# Adafruit_NeoPixel_Ring_16_rev_C.net
KiCad netlist of a schematic drawn in EAGLE
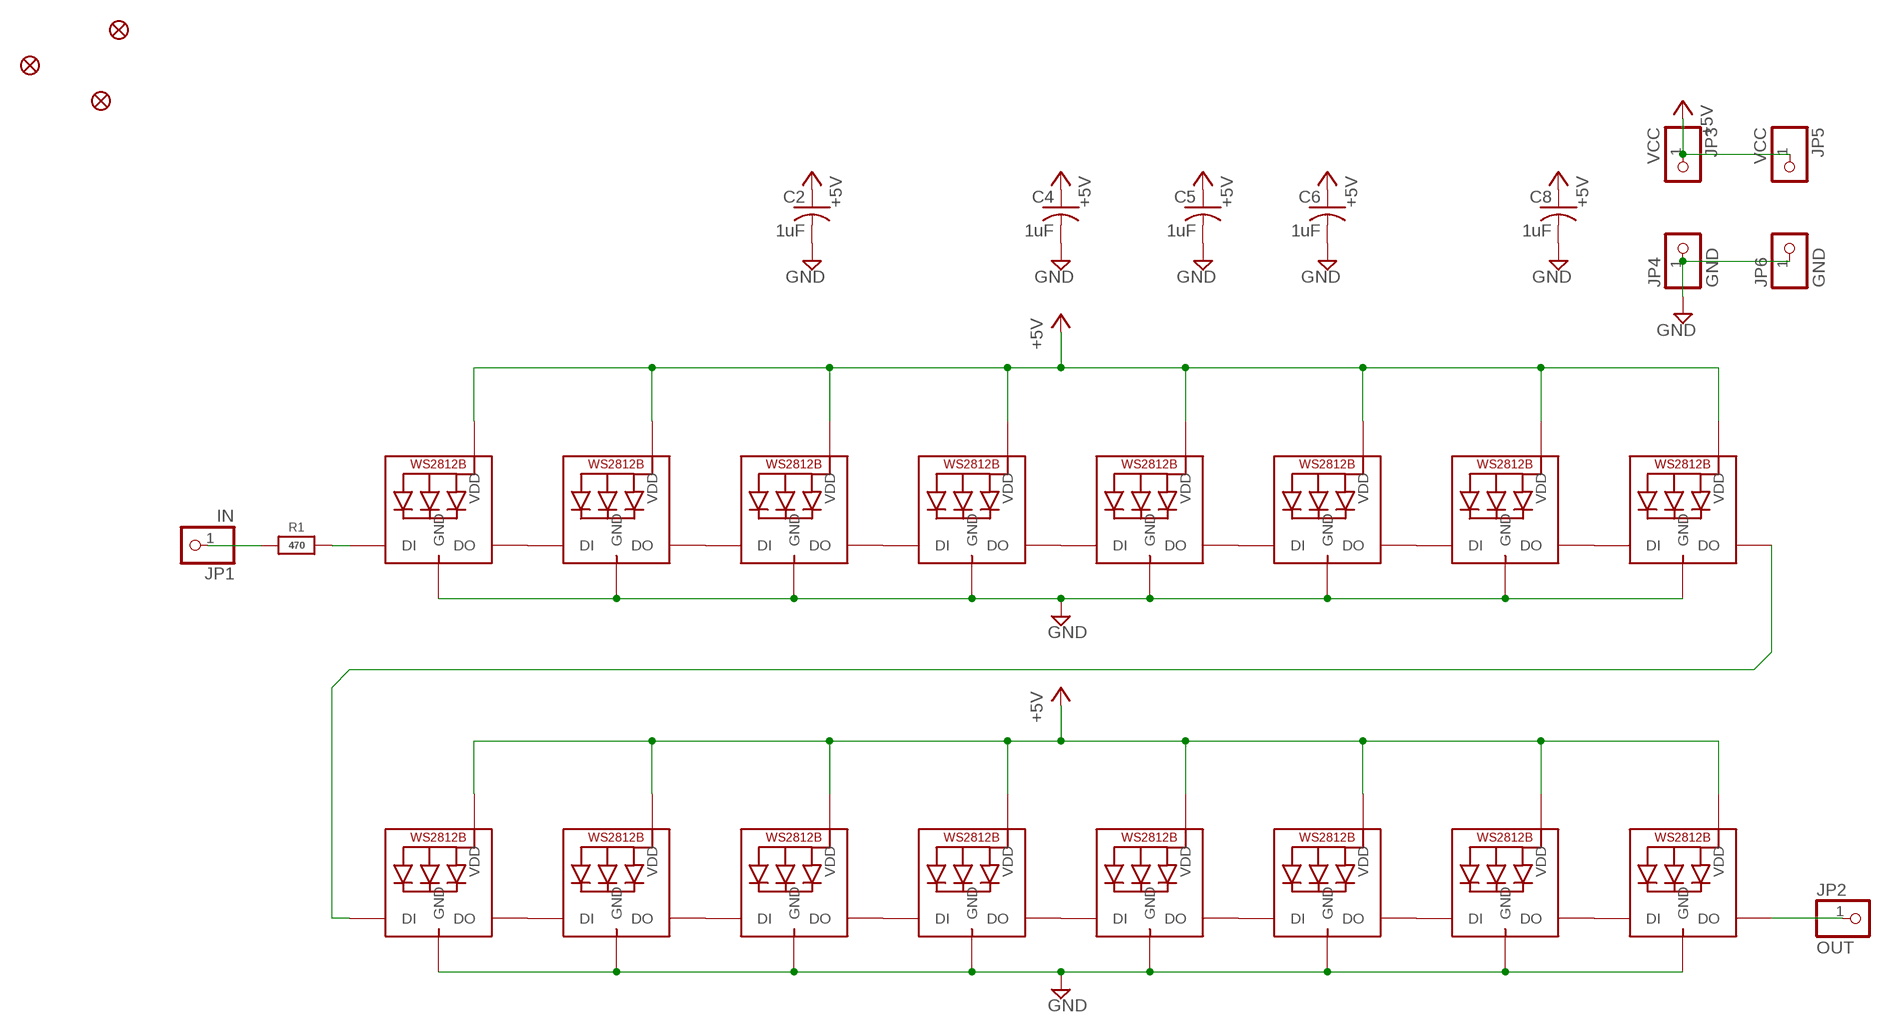
[diagram p0: schematic, sheet 1]

(export (version "E")
  (design (tool "Eeschema 10.0.6"))
  (components
    (comp (ref "C2")
      (value "1uF")
      (footprint "eagle-import:C0603K")
      (libsource (lib "eagle-import") (part "C-USC0603K"))
    )
    (comp (ref "C4")
      (value "1uF")
      (footprint "eagle-import:C0603K")
      (libsource (lib "eagle-import") (part "C-USC0603K"))
    )
    (comp (ref "C5")
      (value "1uF")
      (footprint "eagle-import:C0603K")
      (libsource (lib "eagle-import") (part "C-USC0603K"))
    )
    (comp (ref "C6")
      (value "1uF")
      (footprint "eagle-import:C0603K")
      (libsource (lib "eagle-import") (part "C-USC0603K"))
    )
    (comp (ref "C8")
      (value "1uF")
      (footprint "eagle-import:C0603K")
      (libsource (lib "eagle-import") (part "C-USC0603K"))
    )
    (comp (ref "FID1")
      (value "FIDUCIAL_1MM")
      (footprint "eagle-import:FIDUCIAL_1MM")
      (libsource (lib "eagle-import") (part "FIDUCIAL_1MM"))
    )
    (comp (ref "FID2")
      (value "FIDUCIAL_1MM")
      (footprint "eagle-import:FIDUCIAL_1MM")
      (libsource (lib "eagle-import") (part "FIDUCIAL_1MM"))
    )
    (comp (ref "FID3")
      (value "FIDUCIAL_1MM")
      (footprint "eagle-import:FIDUCIAL_1MM")
      (libsource (lib "eagle-import") (part "FIDUCIAL_1MM"))
    )
    (comp (ref "JP1")
      (value "IN")
      (footprint "eagle-import:1X01-CLEANBIG")
      (libsource (lib "eagle-import") (part "PINHD-1X1CB"))
    )
    (comp (ref "JP2")
      (value "OUT")
      (footprint "eagle-import:1X01-CLEANBIG")
      (libsource (lib "eagle-import") (part "PINHD-1X1CB"))
    )
    (comp (ref "JP3")
      (value "VCC")
      (footprint "eagle-import:1X01-CLEANBIG")
      (libsource (lib "eagle-import") (part "PINHD-1X1CB"))
    )
    (comp (ref "JP4")
      (value "GND")
      (footprint "eagle-import:1X01-CLEANBIG")
      (libsource (lib "eagle-import") (part "PINHD-1X1CB"))
    )
    (comp (ref "JP5")
      (value "VCC")
      (footprint "eagle-import:1X01-CLEANBIG")
      (libsource (lib "eagle-import") (part "PINHD-1X1CB"))
    )
    (comp (ref "JP6")
      (value "GND")
      (footprint "eagle-import:1X01-CLEANBIG")
      (libsource (lib "eagle-import") (part "PINHD-1X1CB"))
    )
    (comp (ref "LED1")
      (value "WS2812B_5050N")
      (footprint "eagle-import:WS2812B-NARROW")
      (libsource (lib "eagle-import") (part "WS2812B_5050N"))
    )
    (comp (ref "LED2")
      (value "WS2812B_5050N")
      (footprint "eagle-import:WS2812B-NARROW")
      (libsource (lib "eagle-import") (part "WS2812B_5050N"))
    )
    (comp (ref "LED3")
      (value "WS2812B_5050N")
      (footprint "eagle-import:WS2812B-NARROW")
      (libsource (lib "eagle-import") (part "WS2812B_5050N"))
    )
    (comp (ref "LED4")
      (value "WS2812B_5050N")
      (footprint "eagle-import:WS2812B-NARROW")
      (libsource (lib "eagle-import") (part "WS2812B_5050N"))
    )
    (comp (ref "LED5")
      (value "WS2812B_5050N")
      (footprint "eagle-import:WS2812B-NARROW")
      (libsource (lib "eagle-import") (part "WS2812B_5050N"))
    )
    (comp (ref "LED6")
      (value "WS2812B_5050N")
      (footprint "eagle-import:WS2812B-NARROW")
      (libsource (lib "eagle-import") (part "WS2812B_5050N"))
    )
    (comp (ref "LED7")
      (value "WS2812B_5050N")
      (footprint "eagle-import:WS2812B-NARROW")
      (libsource (lib "eagle-import") (part "WS2812B_5050N"))
    )
    (comp (ref "LED8")
      (value "WS2812B_5050N")
      (footprint "eagle-import:WS2812B-NARROW")
      (libsource (lib "eagle-import") (part "WS2812B_5050N"))
    )
    (comp (ref "LED9")
      (value "WS2812B_5050N")
      (footprint "eagle-import:WS2812B-NARROW")
      (libsource (lib "eagle-import") (part "WS2812B_5050N"))
    )
    (comp (ref "LED10")
      (value "WS2812B_5050N")
      (footprint "eagle-import:WS2812B-NARROW")
      (libsource (lib "eagle-import") (part "WS2812B_5050N"))
    )
    (comp (ref "LED11")
      (value "WS2812B_5050N")
      (footprint "eagle-import:WS2812B-NARROW")
      (libsource (lib "eagle-import") (part "WS2812B_5050N"))
    )
    (comp (ref "LED12")
      (value "WS2812B_5050N")
      (footprint "eagle-import:WS2812B-NARROW")
      (libsource (lib "eagle-import") (part "WS2812B_5050N"))
    )
    (comp (ref "LED13")
      (value "WS2812B_5050N")
      (footprint "eagle-import:WS2812B-NARROW")
      (libsource (lib "eagle-import") (part "WS2812B_5050N"))
    )
    (comp (ref "LED14")
      (value "WS2812B_5050N")
      (footprint "eagle-import:WS2812B-NARROW")
      (libsource (lib "eagle-import") (part "WS2812B_5050N"))
    )
    (comp (ref "LED15")
      (value "WS2812B_5050N")
      (footprint "eagle-import:WS2812B-NARROW")
      (libsource (lib "eagle-import") (part "WS2812B_5050N"))
    )
    (comp (ref "LED16")
      (value "WS2812B_5050N")
      (footprint "eagle-import:WS2812B-NARROW")
      (libsource (lib "eagle-import") (part "WS2812B_5050N"))
    )
    (comp (ref "R1")
      (value "470")
      (footprint "eagle-import:0603-NO")
      (libsource (lib "eagle-import") (part "RESISTOR_0603_NOOUT"))
    )
  )
  (nets
    (net (code "1") (name "+5V") (class "Default")
      (node (ref "C2") (pin "1") (pinfunction "1_1") (pintype "passive"))
      (node (ref "C4") (pin "1") (pinfunction "1_1") (pintype "passive"))
      (node (ref "C5") (pin "1") (pinfunction "1_1") (pintype "passive"))
      (node (ref "C6") (pin "1") (pinfunction "1_1") (pintype "passive"))
      (node (ref "C8") (pin "1") (pinfunction "1_1") (pintype "passive"))
      (node (ref "JP3") (pin "1") (pinfunction "1_1") (pintype "passive"))
      (node (ref "JP5") (pin "1") (pinfunction "1_1") (pintype "passive"))
      (node (ref "LED1") (pin "1-VDD") (pinfunction "VDD_1-VDD") (pintype "power_in"))
      (node (ref "LED10") (pin "1-VDD") (pinfunction "VDD_1-VDD") (pintype "power_in"))
      (node (ref "LED11") (pin "1-VDD") (pinfunction "VDD_1-VDD") (pintype "power_in"))
      (node (ref "LED12") (pin "1-VDD") (pinfunction "VDD_1-VDD") (pintype "power_in"))
      (node (ref "LED13") (pin "1-VDD") (pinfunction "VDD_1-VDD") (pintype "power_in"))
      (node (ref "LED14") (pin "1-VDD") (pinfunction "VDD_1-VDD") (pintype "power_in"))
      (node (ref "LED15") (pin "1-VDD") (pinfunction "VDD_1-VDD") (pintype "power_in"))
      (node (ref "LED16") (pin "1-VDD") (pinfunction "VDD_1-VDD") (pintype "power_in"))
      (node (ref "LED2") (pin "1-VDD") (pinfunction "VDD_1-VDD") (pintype "power_in"))
      (node (ref "LED3") (pin "1-VDD") (pinfunction "VDD_1-VDD") (pintype "power_in"))
      (node (ref "LED4") (pin "1-VDD") (pinfunction "VDD_1-VDD") (pintype "power_in"))
      (node (ref "LED5") (pin "1-VDD") (pinfunction "VDD_1-VDD") (pintype "power_in"))
      (node (ref "LED6") (pin "1-VDD") (pinfunction "VDD_1-VDD") (pintype "power_in"))
      (node (ref "LED7") (pin "1-VDD") (pinfunction "VDD_1-VDD") (pintype "power_in"))
      (node (ref "LED8") (pin "1-VDD") (pinfunction "VDD_1-VDD") (pintype "power_in"))
      (node (ref "LED9") (pin "1-VDD") (pinfunction "VDD_1-VDD") (pintype "power_in"))
    )
    (net (code "2") (name "GND") (class "Default")
      (node (ref "C2") (pin "2") (pinfunction "2_2") (pintype "passive"))
      (node (ref "C4") (pin "2") (pinfunction "2_2") (pintype "passive"))
      (node (ref "C5") (pin "2") (pinfunction "2_2") (pintype "passive"))
      (node (ref "C6") (pin "2") (pinfunction "2_2") (pintype "passive"))
      (node (ref "C8") (pin "2") (pinfunction "2_2") (pintype "passive"))
      (node (ref "JP4") (pin "1") (pinfunction "1_1") (pintype "passive"))
      (node (ref "JP6") (pin "1") (pinfunction "1_1") (pintype "passive"))
      (node (ref "LED1") (pin "3-GND") (pinfunction "GND_3-GND") (pintype "power_in"))
      (node (ref "LED10") (pin "3-GND") (pinfunction "GND_3-GND") (pintype "power_in"))
      (node (ref "LED11") (pin "3-GND") (pinfunction "GND_3-GND") (pintype "power_in"))
      (node (ref "LED12") (pin "3-GND") (pinfunction "GND_3-GND") (pintype "power_in"))
      (node (ref "LED13") (pin "3-GND") (pinfunction "GND_3-GND") (pintype "power_in"))
      (node (ref "LED14") (pin "3-GND") (pinfunction "GND_3-GND") (pintype "power_in"))
      (node (ref "LED15") (pin "3-GND") (pinfunction "GND_3-GND") (pintype "power_in"))
      (node (ref "LED16") (pin "3-GND") (pinfunction "GND_3-GND") (pintype "power_in"))
      (node (ref "LED2") (pin "3-GND") (pinfunction "GND_3-GND") (pintype "power_in"))
      (node (ref "LED3") (pin "3-GND") (pinfunction "GND_3-GND") (pintype "power_in"))
      (node (ref "LED4") (pin "3-GND") (pinfunction "GND_3-GND") (pintype "power_in"))
      (node (ref "LED5") (pin "3-GND") (pinfunction "GND_3-GND") (pintype "power_in"))
      (node (ref "LED6") (pin "3-GND") (pinfunction "GND_3-GND") (pintype "power_in"))
      (node (ref "LED7") (pin "3-GND") (pinfunction "GND_3-GND") (pintype "power_in"))
      (node (ref "LED8") (pin "3-GND") (pinfunction "GND_3-GND") (pintype "power_in"))
      (node (ref "LED9") (pin "3-GND") (pinfunction "GND_3-GND") (pintype "power_in"))
    )
    (net (code "3") (name "Net-(JP1-Pad1)") (class "Default")
      (node (ref "JP1") (pin "1") (pinfunction "1_1") (pintype "passive"))
      (node (ref "R1") (pin "1") (pinfunction "1_1") (pintype "passive"))
    )
    (net (code "4") (name "Net-(LED1-DI)") (class "Default")
      (node (ref "LED1") (pin "4-DIN") (pinfunction "DI_4-DIN") (pintype "input"))
      (node (ref "R1") (pin "2") (pinfunction "2_2") (pintype "passive"))
    )
    (net (code "5") (name "Net-(LED1-DO)") (class "Default")
      (node (ref "LED1") (pin "2-DOUT") (pinfunction "DO_2-DOUT") (pintype "output"))
      (node (ref "LED2") (pin "4-DIN") (pinfunction "DI_4-DIN") (pintype "input"))
    )
    (net (code "6") (name "Net-(LED2-DO)") (class "Default")
      (node (ref "LED2") (pin "2-DOUT") (pinfunction "DO_2-DOUT") (pintype "output"))
      (node (ref "LED3") (pin "4-DIN") (pinfunction "DI_4-DIN") (pintype "input"))
    )
    (net (code "7") (name "Net-(LED3-DO)") (class "Default")
      (node (ref "LED3") (pin "2-DOUT") (pinfunction "DO_2-DOUT") (pintype "output"))
      (node (ref "LED4") (pin "4-DIN") (pinfunction "DI_4-DIN") (pintype "input"))
    )
    (net (code "8") (name "Net-(LED4-DO)") (class "Default")
      (node (ref "LED4") (pin "2-DOUT") (pinfunction "DO_2-DOUT") (pintype "output"))
      (node (ref "LED5") (pin "4-DIN") (pinfunction "DI_4-DIN") (pintype "input"))
    )
    (net (code "9") (name "Net-(LED5-DO)") (class "Default")
      (node (ref "LED5") (pin "2-DOUT") (pinfunction "DO_2-DOUT") (pintype "output"))
      (node (ref "LED6") (pin "4-DIN") (pinfunction "DI_4-DIN") (pintype "input"))
    )
    (net (code "10") (name "Net-(LED6-DO)") (class "Default")
      (node (ref "LED6") (pin "2-DOUT") (pinfunction "DO_2-DOUT") (pintype "output"))
      (node (ref "LED7") (pin "4-DIN") (pinfunction "DI_4-DIN") (pintype "input"))
    )
    (net (code "11") (name "Net-(LED7-DO)") (class "Default")
      (node (ref "LED7") (pin "2-DOUT") (pinfunction "DO_2-DOUT") (pintype "output"))
      (node (ref "LED8") (pin "4-DIN") (pinfunction "DI_4-DIN") (pintype "input"))
    )
    (net (code "12") (name "Net-(LED8-DO)") (class "Default")
      (node (ref "LED8") (pin "2-DOUT") (pinfunction "DO_2-DOUT") (pintype "output"))
      (node (ref "LED9") (pin "4-DIN") (pinfunction "DI_4-DIN") (pintype "input"))
    )
    (net (code "13") (name "Net-(LED10-DI)") (class "Default")
      (node (ref "LED10") (pin "4-DIN") (pinfunction "DI_4-DIN") (pintype "input"))
      (node (ref "LED9") (pin "2-DOUT") (pinfunction "DO_2-DOUT") (pintype "output"))
    )
    (net (code "14") (name "Net-(LED10-DO)") (class "Default")
      (node (ref "LED10") (pin "2-DOUT") (pinfunction "DO_2-DOUT") (pintype "output"))
      (node (ref "LED11") (pin "4-DIN") (pinfunction "DI_4-DIN") (pintype "input"))
    )
    (net (code "15") (name "Net-(LED11-DO)") (class "Default")
      (node (ref "LED11") (pin "2-DOUT") (pinfunction "DO_2-DOUT") (pintype "output"))
      (node (ref "LED12") (pin "4-DIN") (pinfunction "DI_4-DIN") (pintype "input"))
    )
    (net (code "16") (name "Net-(LED12-DO)") (class "Default")
      (node (ref "LED12") (pin "2-DOUT") (pinfunction "DO_2-DOUT") (pintype "output"))
      (node (ref "LED13") (pin "4-DIN") (pinfunction "DI_4-DIN") (pintype "input"))
    )
    (net (code "17") (name "Net-(LED13-DO)") (class "Default")
      (node (ref "LED13") (pin "2-DOUT") (pinfunction "DO_2-DOUT") (pintype "output"))
      (node (ref "LED14") (pin "4-DIN") (pinfunction "DI_4-DIN") (pintype "input"))
    )
    (net (code "18") (name "Net-(LED14-DO)") (class "Default")
      (node (ref "LED14") (pin "2-DOUT") (pinfunction "DO_2-DOUT") (pintype "output"))
      (node (ref "LED15") (pin "4-DIN") (pinfunction "DI_4-DIN") (pintype "input"))
    )
    (net (code "19") (name "Net-(LED15-DO)") (class "Default")
      (node (ref "LED15") (pin "2-DOUT") (pinfunction "DO_2-DOUT") (pintype "output"))
      (node (ref "LED16") (pin "4-DIN") (pinfunction "DI_4-DIN") (pintype "input"))
    )
    (net (code "20") (name "Net-(LED16-DO)") (class "Default")
      (node (ref "JP2") (pin "1") (pinfunction "1_1") (pintype "passive"))
      (node (ref "LED16") (pin "2-DOUT") (pinfunction "DO_2-DOUT") (pintype "output"))
    )
  )
)
